# HM-RC-8_Remote-v01-008.net
KiCad netlist of a schematic drawn in EAGLE
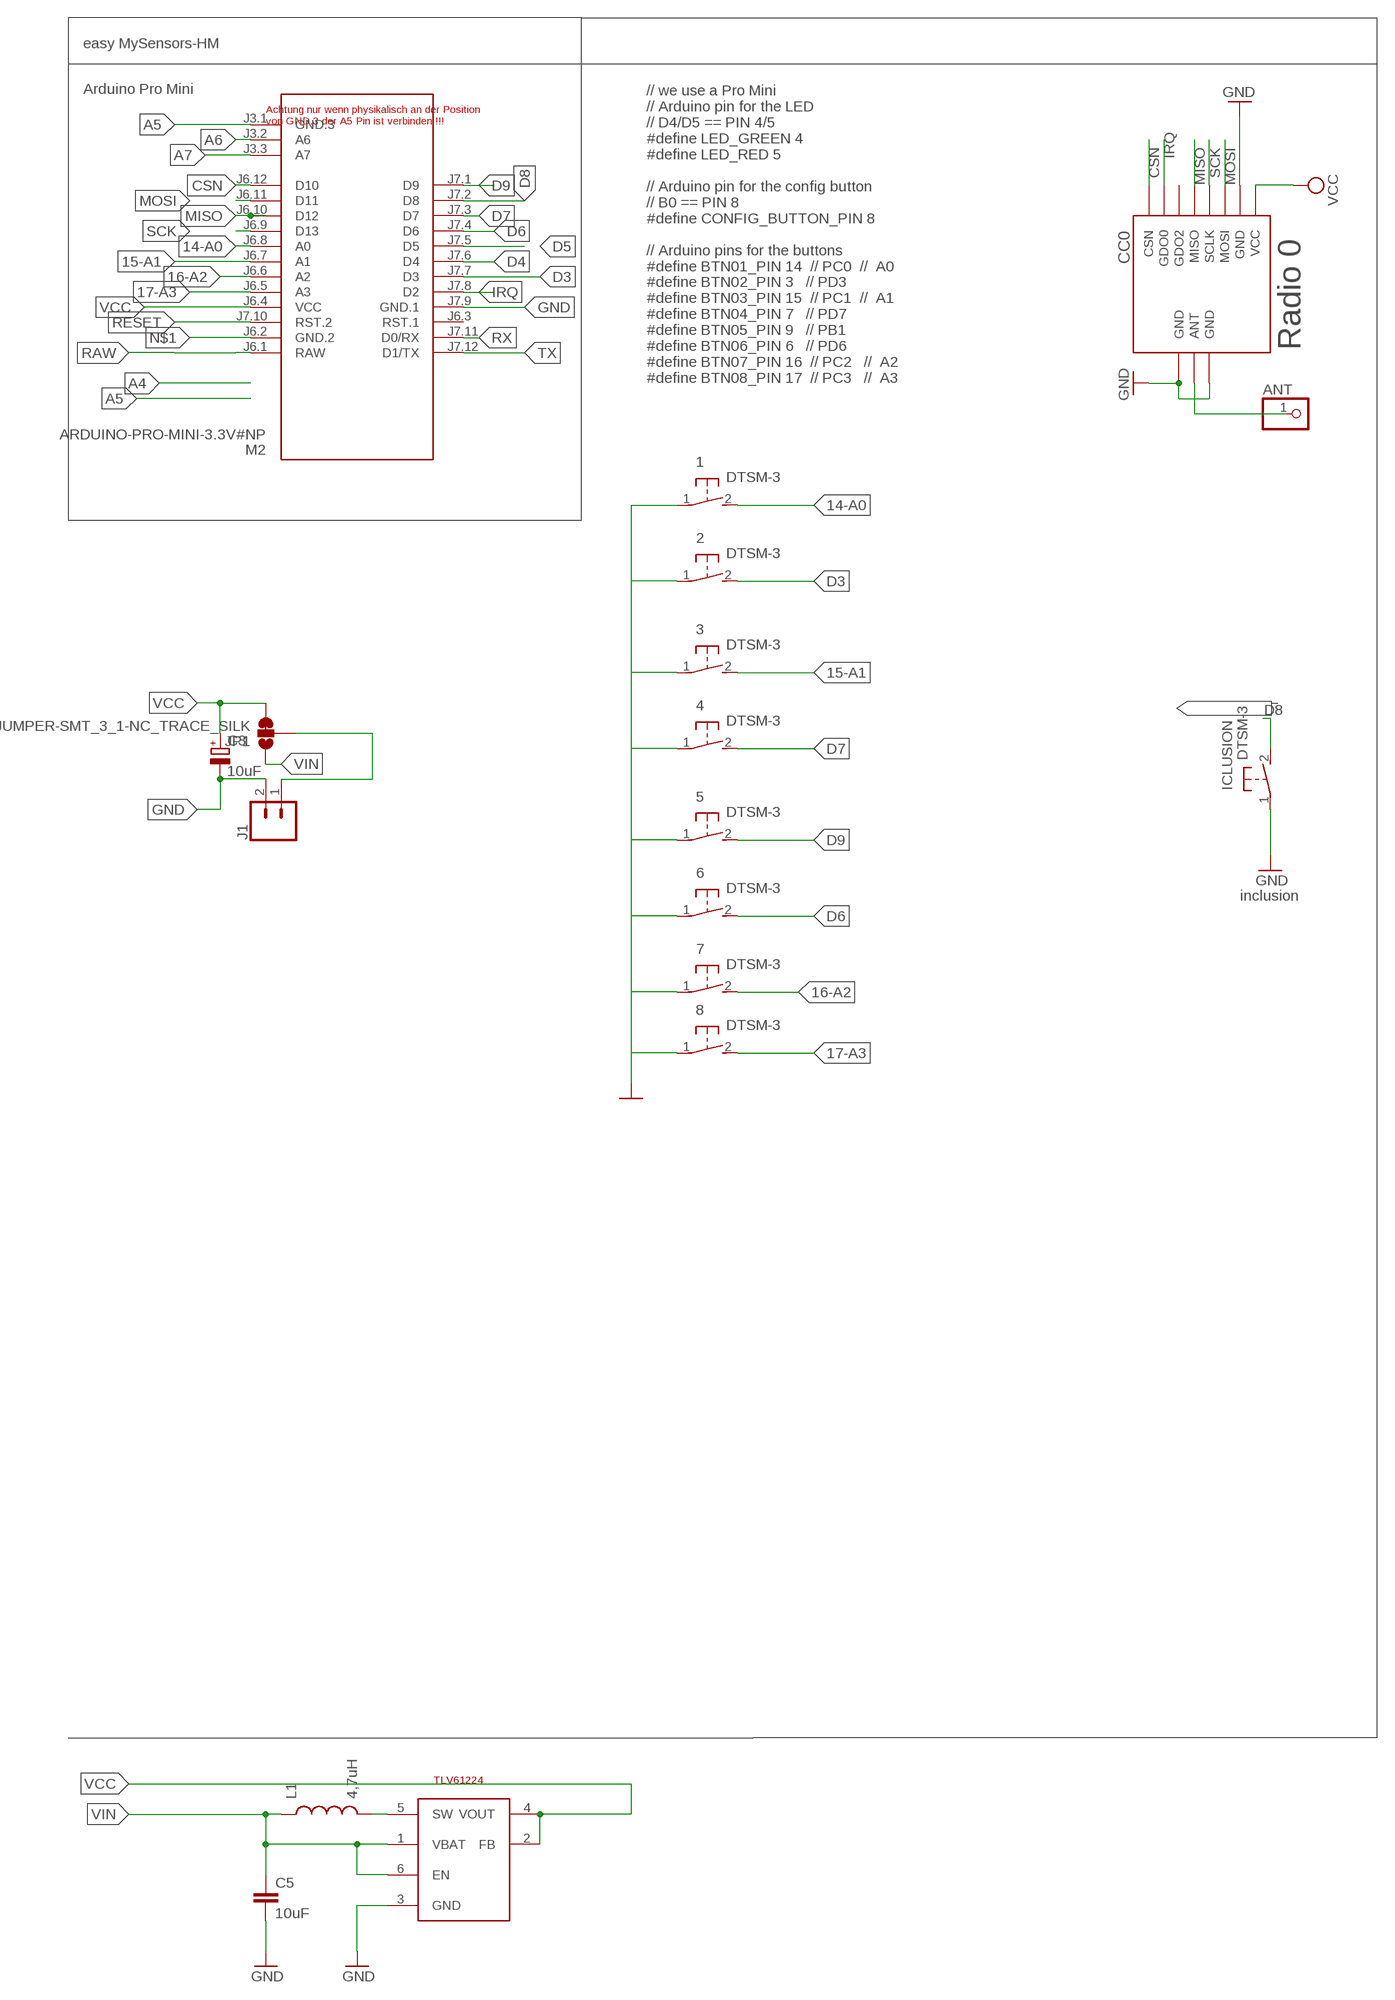
[diagram p0: schematic, sheet 1]

(export (version "E")
  (design (tool "Eeschema 10.0.6"))
  (components
    (comp (ref "1")
      (value "DTSM-3")
      (footprint "eagle-import:DTSM-3")
      (libsource (lib "eagle-import") (part "DTSM-3"))
    )
    (comp (ref "2")
      (value "DTSM-3")
      (footprint "eagle-import:DTSM-3")
      (libsource (lib "eagle-import") (part "DTSM-3"))
    )
    (comp (ref "3")
      (value "DTSM-3")
      (footprint "eagle-import:DTSM-3")
      (libsource (lib "eagle-import") (part "DTSM-3"))
    )
    (comp (ref "4")
      (value "DTSM-3")
      (footprint "eagle-import:DTSM-3")
      (libsource (lib "eagle-import") (part "DTSM-3"))
    )
    (comp (ref "5")
      (value "DTSM-3")
      (footprint "eagle-import:DTSM-3")
      (libsource (lib "eagle-import") (part "DTSM-3"))
    )
    (comp (ref "6")
      (value "DTSM-3")
      (footprint "eagle-import:DTSM-3")
      (libsource (lib "eagle-import") (part "DTSM-3"))
    )
    (comp (ref "7")
      (value "DTSM-3")
      (footprint "eagle-import:DTSM-3")
      (libsource (lib "eagle-import") (part "DTSM-3"))
    )
    (comp (ref "8")
      (value "DTSM-3")
      (footprint "eagle-import:DTSM-3")
      (libsource (lib "eagle-import") (part "DTSM-3"))
    )
    (comp (ref "ANT")
      (value "PINHD-1X1")
      (footprint "eagle-import:1X01")
      (libsource (lib "eagle-import") (part "PINHD-1X1"))
    )
    (comp (ref "C3")
      (value "10uF")
      (footprint "eagle-import:SMC_C")
      (libsource (lib "eagle-import") (part "CPOL-EUSMCC"))
    )
    (comp (ref "C5")
      (value "10uF")
      (footprint "eagle-import:0805")
      (libsource (lib "eagle-import") (part "CAP0805"))
    )
    (comp (ref "CC0")
      (value "CC1101")
      (footprint "eagle-import:CC1101_MODULE1_SMD")
      (libsource (lib "eagle-import") (part "CC1101_MODULE1SMD"))
    )
    (comp (ref "ICLUSION")
      (value "DTSM-3")
      (footprint "eagle-import:DTSM-3")
      (libsource (lib "eagle-import") (part "DTSM-3"))
    )
    (comp (ref "J1")
      (value "CONN_02PTH3")
      (footprint "eagle-import:1X02_LONGPADS")
      (libsource (lib "eagle-import") (part "CONN_02PTH3"))
    )
    (comp (ref "JP1")
      (value "JUMPER-SMT_3_1-NC_TRACE_SILK")
      (footprint "eagle-import:SMT-JUMPER_3_1-NC_TRACE_SILK")
      (libsource (lib "eagle-import") (part "JUMPER-SMT_3_1-NC_TRACE_SILK"))
    )
    (comp (ref "L1")
      (value "4,7uH")
      (footprint "eagle-import:0805")
      (libsource (lib "eagle-import") (part "INDUCTOR0805"))
    )
    (comp (ref "M2")
      (value "ARDUINO-PRO-MINI-3.3V#NP")
      (footprint "eagle-import:ARDUINO-PRO-MINI#NP")
      (libsource (lib "eagle-import") (part "ARDUINO-PRO-MINI-#NP3.3V"))
    )
    (comp (ref "STEPUP")
      (value "TLV61224")
      (footprint "eagle-import:SOT23-6L")
      (libsource (lib "eagle-import") (part "TI-TLV61224"))
    )
  )
  (nets
    (net (code "1") (name "14-A0") (class "Default")
      (node (ref "1") (pin "2") (pinfunction "2_2") (pintype "passive"))
      (node (ref "M2") (pin "J6.8") (pinfunction "A0_J6.8") (pintype "bidirectional"))
    )
    (net (code "2") (name "15-A1") (class "Default")
      (node (ref "3") (pin "2") (pinfunction "2_2") (pintype "passive"))
      (node (ref "M2") (pin "J6.7") (pinfunction "A1_J6.7") (pintype "bidirectional"))
    )
    (net (code "3") (name "16-A2") (class "Default")
      (node (ref "7") (pin "2") (pinfunction "2_2") (pintype "passive"))
      (node (ref "M2") (pin "J6.6") (pinfunction "A2_J6.6") (pintype "bidirectional"))
    )
    (net (code "4") (name "17-A3") (class "Default")
      (node (ref "8") (pin "2") (pinfunction "2_2") (pintype "passive"))
      (node (ref "M2") (pin "J6.5") (pinfunction "A3_J6.5") (pintype "bidirectional"))
    )
    (net (code "6") (name "A5") (class "Default")
      (node (ref "M2") (pin "J3.1") (pinfunction "GND.3_J3.1") (pintype "bidirectional"))
    )
    (net (code "7") (name "A6") (class "Default")
      (node (ref "M2") (pin "J3.2") (pinfunction "A6_J3.2") (pintype "bidirectional"))
    )
    (net (code "8") (name "A7") (class "Default")
      (node (ref "M2") (pin "J3.3") (pinfunction "A7_J3.3") (pintype "bidirectional"))
    )
    (net (code "9") (name "CSN") (class "Default")
      (node (ref "CC0") (pin "CSN") (pinfunction "CSN_CSN") (pintype "bidirectional"))
      (node (ref "M2") (pin "J6.12") (pinfunction "D10_J6.12") (pintype "bidirectional"))
    )
    (net (code "10") (name "D3") (class "Default")
      (node (ref "2") (pin "2") (pinfunction "2_2") (pintype "passive"))
      (node (ref "M2") (pin "J7.7") (pinfunction "D3_J7.7") (pintype "bidirectional"))
    )
    (net (code "11") (name "D4") (class "Default")
      (node (ref "M2") (pin "J7.6") (pinfunction "D4_J7.6") (pintype "bidirectional"))
    )
    (net (code "12") (name "D5") (class "Default")
      (node (ref "M2") (pin "J7.5") (pinfunction "D5_J7.5") (pintype "bidirectional"))
    )
    (net (code "13") (name "D6") (class "Default")
      (node (ref "6") (pin "2") (pinfunction "2_2") (pintype "passive"))
      (node (ref "M2") (pin "J7.4") (pinfunction "D6_J7.4") (pintype "bidirectional"))
    )
    (net (code "14") (name "D7") (class "Default")
      (node (ref "4") (pin "2") (pinfunction "2_2") (pintype "passive"))
      (node (ref "M2") (pin "J7.3") (pinfunction "D7_J7.3") (pintype "bidirectional"))
    )
    (net (code "15") (name "D8") (class "Default")
      (node (ref "ICLUSION") (pin "2") (pinfunction "2_2") (pintype "passive"))
      (node (ref "M2") (pin "J7.2") (pinfunction "D8_J7.2") (pintype "bidirectional"))
    )
    (net (code "16") (name "D9") (class "Default")
      (node (ref "5") (pin "2") (pinfunction "2_2") (pintype "passive"))
      (node (ref "M2") (pin "J7.1") (pinfunction "D9_J7.1") (pintype "bidirectional"))
    )
    (net (code "17") (name "GND") (class "Default")
      (node (ref "1") (pin "1") (pinfunction "1_1") (pintype "passive"))
      (node (ref "3") (pin "1") (pinfunction "1_1") (pintype "passive"))
      (node (ref "4") (pin "1") (pinfunction "1_1") (pintype "passive"))
      (node (ref "5") (pin "1") (pinfunction "1_1") (pintype "passive"))
      (node (ref "6") (pin "1") (pinfunction "1_1") (pintype "passive"))
      (node (ref "7") (pin "1") (pinfunction "1_1") (pintype "passive"))
      (node (ref "8") (pin "1") (pinfunction "1_1") (pintype "passive"))
      (node (ref "C3") (pin "-") (pinfunction "-_-") (pintype "passive"))
      (node (ref "C5") (pin "2") (pinfunction "2_2") (pintype "passive"))
      (node (ref "CC0") (pin "GND@0") (pinfunction "GND_GND@0") (pintype "power_in"))
      (node (ref "CC0") (pin "GND@1") (pinfunction "GND_GND@1") (pintype "power_in"))
      (node (ref "CC0") (pin "GND@2") (pinfunction "GND_GND@2") (pintype "power_in"))
      (node (ref "ICLUSION") (pin "1") (pinfunction "1_1") (pintype "passive"))
      (node (ref "J1") (pin "2") (pinfunction "2_2") (pintype "passive"))
      (node (ref "M2") (pin "J7.9") (pinfunction "GND.1_J7.9") (pintype "power_in"))
      (node (ref "STEPUP") (pin "3") (pinfunction "GND_3") (pintype "power_in"))
    )
    (net (code "18") (name "IRQ") (class "Default")
      (node (ref "CC0") (pin "GDO0") (pinfunction "GDO0_GDO0") (pintype "bidirectional"))
      (node (ref "M2") (pin "J7.8") (pinfunction "D2_J7.8") (pintype "bidirectional"))
    )
    (net (code "19") (name "MISO") (class "Default")
      (node (ref "CC0") (pin "MISO") (pinfunction "MISO_MISO") (pintype "bidirectional"))
      (node (ref "M2") (pin "J6.10") (pinfunction "D12_J6.10") (pintype "bidirectional"))
    )
    (net (code "20") (name "MOSI") (class "Default")
      (node (ref "CC0") (pin "MOSI") (pinfunction "MOSI_MOSI") (pintype "bidirectional"))
      (node (ref "M2") (pin "J6.11") (pinfunction "D11_J6.11") (pintype "bidirectional"))
    )
    (net (code "21") (name "N$1") (class "Default")
      (node (ref "M2") (pin "J6.2") (pinfunction "GND.2_J6.2") (pintype "power_in"))
    )
    (net (code "22") (name "Net-(ANT-Pad1)") (class "Default")
      (node (ref "ANT") (pin "1") (pinfunction "1_1") (pintype "passive"))
      (node (ref "CC0") (pin "ANT") (pinfunction "ANT_ANT") (pintype "output"))
    )
    (net (code "23") (name "Net-(J1-Pad1)") (class "Default")
      (node (ref "J1") (pin "1") (pinfunction "1_1") (pintype "passive"))
      (node (ref "JP1") (pin "2") (pinfunction "2_2") (pintype "passive"))
    )
    (net (code "24") (name "Net-(STEPUP-SW)") (class "Default")
      (node (ref "L1") (pin "2") (pinfunction "2_2") (pintype "passive"))
      (node (ref "STEPUP") (pin "5") (pinfunction "SW_5") (pintype "power_in"))
    )
    (net (code "25") (name "RAW") (class "Default")
      (node (ref "M2") (pin "J6.1") (pinfunction "RAW_J6.1") (pintype "power_in"))
    )
    (net (code "26") (name "RESET") (class "Default")
      (node (ref "M2") (pin "J7.10") (pinfunction "RST.2_J7.10") (pintype "bidirectional"))
    )
    (net (code "27") (name "RX") (class "Default")
      (node (ref "M2") (pin "J7.11") (pinfunction "D0/RX_J7.11") (pintype "bidirectional"))
    )
    (net (code "28") (name "SCK") (class "Default")
      (node (ref "CC0") (pin "SCLK") (pinfunction "SCLK_SCLK") (pintype "bidirectional"))
      (node (ref "M2") (pin "J6.9") (pinfunction "D13_J6.9") (pintype "bidirectional"))
    )
    (net (code "29") (name "TX") (class "Default")
      (node (ref "M2") (pin "J7.12") (pinfunction "D1/TX_J7.12") (pintype "bidirectional"))
    )
    (net (code "30") (name "VCC") (class "Default")
      (node (ref "C3") (pin "+") (pinfunction "+_+") (pintype "passive"))
      (node (ref "CC0") (pin "VCC") (pinfunction "VCC_VCC") (pintype "power_in"))
      (node (ref "JP1") (pin "3") (pinfunction "3_3") (pintype "passive"))
      (node (ref "M2") (pin "J6.4") (pinfunction "VCC_J6.4") (pintype "power_in"))
      (node (ref "STEPUP") (pin "2") (pinfunction "FB_2") (pintype "input"))
      (node (ref "STEPUP") (pin "4") (pinfunction "VOUT_4") (pintype "power_in"))
    )
    (net (code "31") (name "VIN") (class "Default")
      (node (ref "C5") (pin "1") (pinfunction "1_1") (pintype "passive"))
      (node (ref "JP1") (pin "1") (pinfunction "1_1") (pintype "passive"))
      (node (ref "L1") (pin "1") (pinfunction "1_1") (pintype "passive"))
      (node (ref "STEPUP") (pin "1") (pinfunction "VBAT_1") (pintype "power_in"))
      (node (ref "STEPUP") (pin "6") (pinfunction "EN_6") (pintype "input"))
    )
    (net (code "32") (name "unconnected-(2-Pad1)") (class "Default")
      (node (ref "2") (pin "1") (pinfunction "1_1") (pintype "passive"))
    )
    (net (code "33") (name "unconnected-(CC0-PadGDO2)") (class "Default")
      (node (ref "CC0") (pin "GDO2") (pinfunction "GDO2_GDO2") (pintype "bidirectional"))
    )
    (net (code "34") (name "unconnected-(M2-RST.1-PadJ6.3)") (class "Default")
      (node (ref "M2") (pin "J6.3") (pinfunction "RST.1_J6.3") (pintype "bidirectional"))
    )
  )
)
